# pcb_tcc_v2.net
KiCad netlist of a schematic drawn in EAGLE
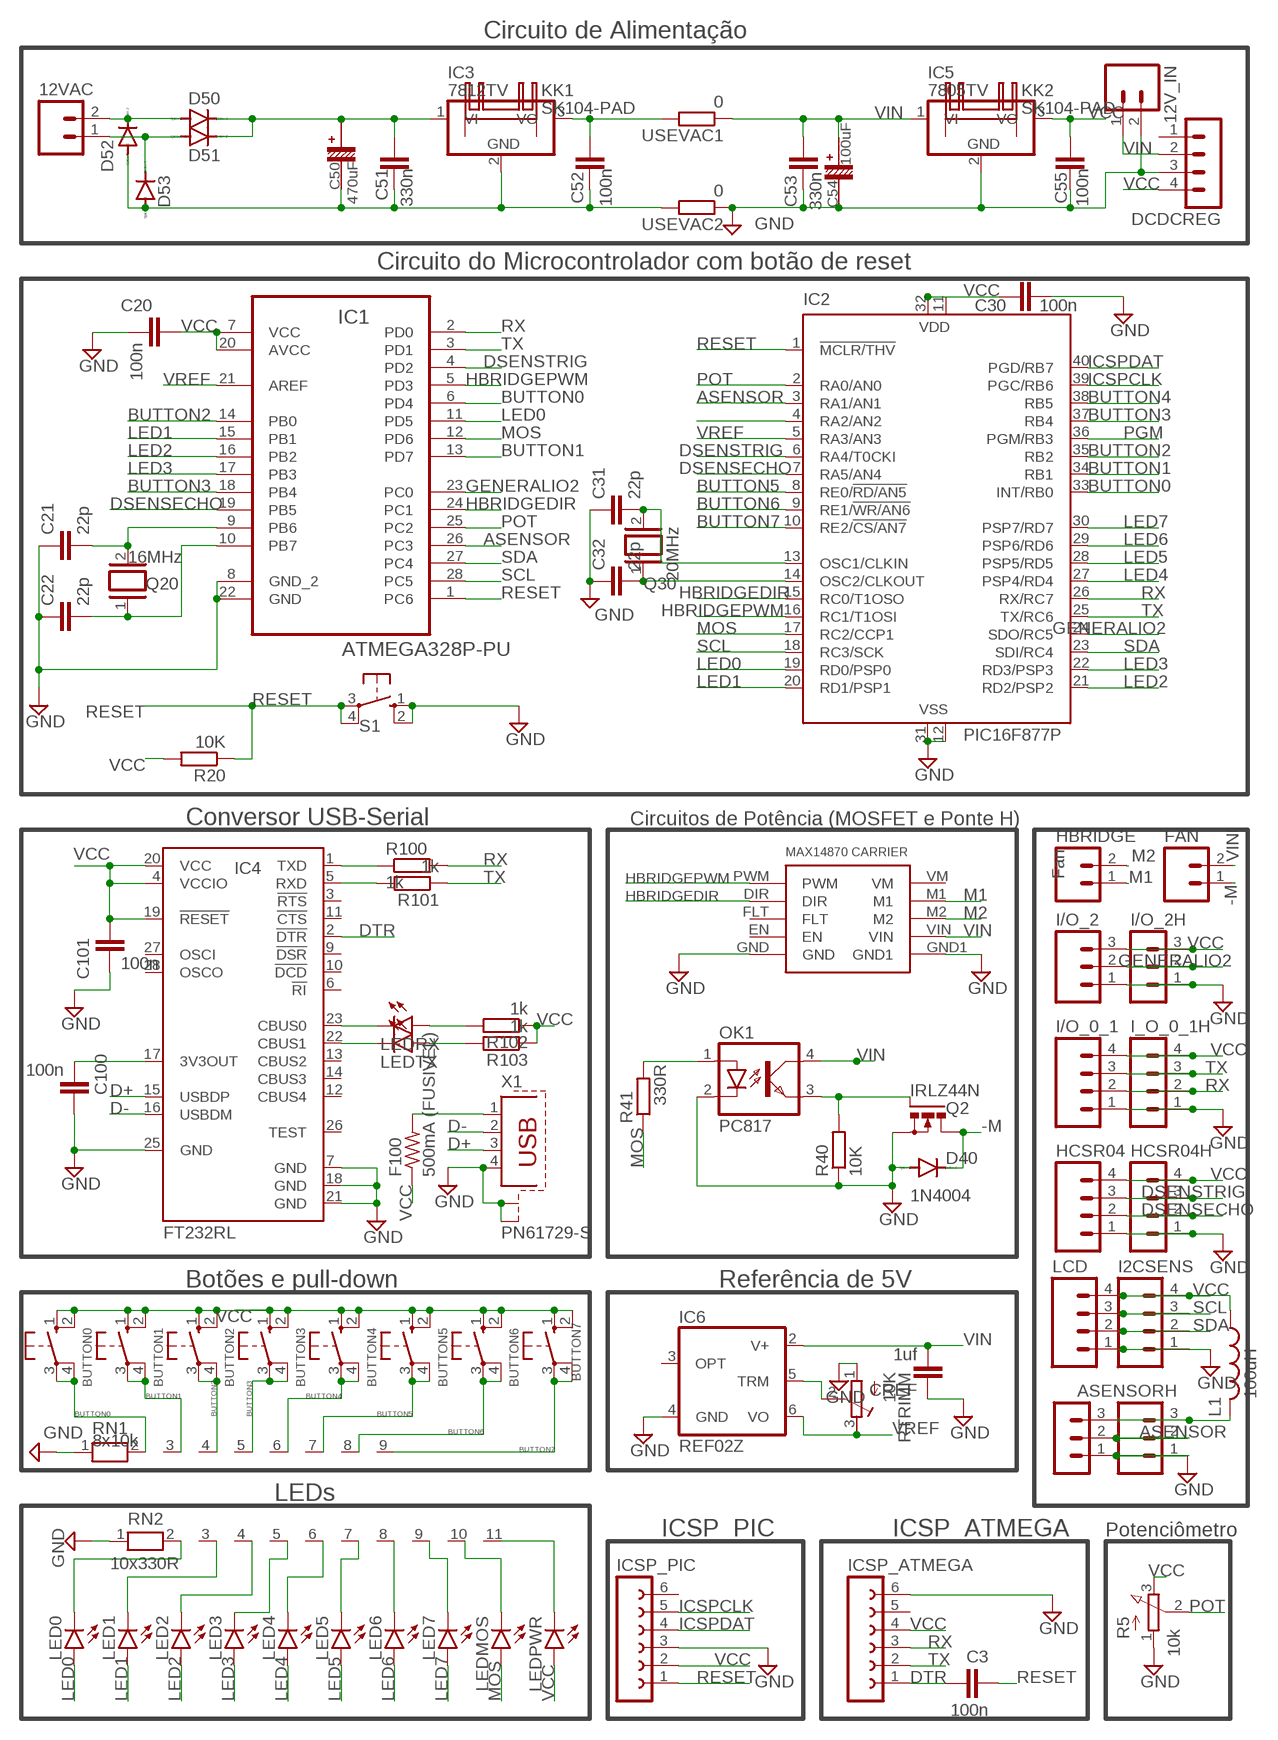
[diagram p0: schematic, sheet 1]

(export (version "E")
  (design (tool "Eeschema 10.0.6"))
  (components
    (comp (ref "12VAC")
      (value "M02")
      (footprint "eagle-import:02P")
      (libsource (lib "eagle-import") (part "M02"))
    )
    (comp (ref "12V_IN")
      (value "M02")
      (footprint "eagle-import:02P")
      (libsource (lib "eagle-import") (part "M02"))
    )
    (comp (ref "ASENSOR")
      (value "M03")
      (footprint "eagle-import:03P")
      (libsource (lib "eagle-import") (part "M03"))
    )
    (comp (ref "ASENSORH")
      (value "MA03-1")
      (footprint "eagle-import:MA03-1")
      (libsource (lib "eagle-import") (part "MA03-1"))
    )
    (comp (ref "BUTTON0")
      (value "10-XX")
      (footprint "eagle-import:B3F-10XX")
      (fields (field (name "MPN") "B3F-1000"))
      (libsource (lib "eagle-import") (part "10-XX"))
    )
    (comp (ref "BUTTON1")
      (value "10-XX")
      (footprint "eagle-import:B3F-10XX")
      (fields (field (name "MPN") "B3F-1000"))
      (libsource (lib "eagle-import") (part "10-XX"))
    )
    (comp (ref "BUTTON2")
      (value "10-XX")
      (footprint "eagle-import:B3F-10XX")
      (fields (field (name "MPN") "B3F-1000"))
      (libsource (lib "eagle-import") (part "10-XX"))
    )
    (comp (ref "BUTTON3")
      (value "10-XX")
      (footprint "eagle-import:B3F-10XX")
      (fields (field (name "MPN") "B3F-1000"))
      (libsource (lib "eagle-import") (part "10-XX"))
    )
    (comp (ref "BUTTON4")
      (value "10-XX")
      (footprint "eagle-import:B3F-10XX")
      (fields (field (name "MPN") "B3F-1000"))
      (libsource (lib "eagle-import") (part "10-XX"))
    )
    (comp (ref "BUTTON5")
      (value "10-XX")
      (footprint "eagle-import:B3F-10XX")
      (fields (field (name "MPN") "B3F-1000"))
      (libsource (lib "eagle-import") (part "10-XX"))
    )
    (comp (ref "BUTTON6")
      (value "10-XX")
      (footprint "eagle-import:B3F-10XX")
      (fields (field (name "MPN") "B3F-1000"))
      (libsource (lib "eagle-import") (part "10-XX"))
    )
    (comp (ref "BUTTON7")
      (value "10-XX")
      (footprint "eagle-import:B3F-10XX")
      (fields (field (name "MPN") "B3F-1000"))
      (libsource (lib "eagle-import") (part "10-XX"))
    )
    (comp (ref "C3")
      (value "100n")
      (footprint "eagle-import:C5B2.5")
      (libsource (lib "eagle-import") (part "C5/2.5"))
    )
    (comp (ref "C20")
      (value "100n")
      (footprint "eagle-import:C5B2.5")
      (libsource (lib "eagle-import") (part "C5/2.5"))
    )
    (comp (ref "C21")
      (value "22p")
      (footprint "eagle-import:C5B2.5")
      (libsource (lib "eagle-import") (part "C5/2.5"))
    )
    (comp (ref "C22")
      (value "22p")
      (footprint "eagle-import:C5B2.5")
      (libsource (lib "eagle-import") (part "C5/2.5"))
    )
    (comp (ref "C30")
      (value "100n")
      (footprint "eagle-import:C5B2.5")
      (libsource (lib "eagle-import") (part "C5/2.5"))
    )
    (comp (ref "C31")
      (value "22p")
      (footprint "eagle-import:C5B2.5")
      (libsource (lib "eagle-import") (part "C5/2.5"))
    )
    (comp (ref "C32")
      (value "22p")
      (footprint "eagle-import:C5B2.5")
      (libsource (lib "eagle-import") (part "C5/2.5"))
    )
    (comp (ref "C50")
      (value "470uF")
      (footprint "eagle-import:16V-10-5.08")
      (libsource (lib "eagle-import") (part "CE-16V-10-5.08"))
    )
    (comp (ref "C51")
      (value "330n")
      (footprint "eagle-import:C5B2.5")
      (libsource (lib "eagle-import") (part "C5/2.5"))
    )
    (comp (ref "C52")
      (value "100n")
      (footprint "eagle-import:C5B2.5")
      (libsource (lib "eagle-import") (part "C5/2.5"))
    )
    (comp (ref "C53")
      (value "330n")
      (footprint "eagle-import:C5B2.5")
      (libsource (lib "eagle-import") (part "C5/2.5"))
    )
    (comp (ref "C54")
      (value "100uF")
      (footprint "eagle-import:16V-6.3-2.54")
      (libsource (lib "eagle-import") (part "CE-16V-06.3-2.54"))
    )
    (comp (ref "C55")
      (value "100n")
      (footprint "eagle-import:C5B2.5")
      (libsource (lib "eagle-import") (part "C5/2.5"))
    )
    (comp (ref "C100")
      (value "100n")
      (footprint "eagle-import:C5B2.5")
      (libsource (lib "eagle-import") (part "C5/2.5"))
    )
    (comp (ref "C101")
      (value "100n")
      (footprint "eagle-import:C5B2.5")
      (libsource (lib "eagle-import") (part "C5/2.5"))
    )
    (comp (ref "CREF")
      (value "1uf")
      (footprint "eagle-import:C2.5-2")
      (libsource (lib "eagle-import") (part "C2.5/2"))
    )
    (comp (ref "D40")
      (value "1N4004")
      (footprint "eagle-import:DO41-10")
      (libsource (lib "eagle-import") (part "1N4004"))
    )
    (comp (ref "D50")
      (value "1N4004")
      (footprint "eagle-import:DO41-10")
      (libsource (lib "eagle-import") (part "1N4004"))
    )
    (comp (ref "D51")
      (value "1N4004")
      (footprint "eagle-import:DO41-10")
      (libsource (lib "eagle-import") (part "1N4004"))
    )
    (comp (ref "D52")
      (value "1N4004")
      (footprint "eagle-import:DO41-10")
      (libsource (lib "eagle-import") (part "1N4004"))
    )
    (comp (ref "D53")
      (value "1N4004")
      (footprint "eagle-import:DO41-10")
      (libsource (lib "eagle-import") (part "1N4004"))
    )
    (comp (ref "DCDCREG")
      (value "MA04-1")
      (footprint "eagle-import:MA04-1")
      (libsource (lib "eagle-import") (part "MA04-1"))
    )
    (comp (ref "F100")
      (value "500mA (FUSIVEL)")
      (footprint "eagle-import:R1206")
      (libsource (lib "eagle-import") (part "R-US_R1206"))
    )
    (comp (ref "FAN")
      (value "M02")
      (footprint "eagle-import:02P")
      (libsource (lib "eagle-import") (part "M02"))
    )
    (comp (ref "HBRIDGE")
      (value "M02")
      (footprint "eagle-import:02P")
      (libsource (lib "eagle-import") (part "M02"))
    )
    (comp (ref "HCSR04")
      (value "M04")
      (footprint "eagle-import:04P")
      (libsource (lib "eagle-import") (part "M04"))
    )
    (comp (ref "HCSR04H")
      (value "MA04-1")
      (footprint "eagle-import:MA04-1")
      (libsource (lib "eagle-import") (part "MA04-1"))
    )
    (comp (ref "I/O_0_1")
      (value "M04")
      (footprint "eagle-import:04P")
      (libsource (lib "eagle-import") (part "M04"))
    )
    (comp (ref "I/O_2")
      (value "M03")
      (footprint "eagle-import:03P")
      (libsource (lib "eagle-import") (part "M03"))
    )
    (comp (ref "I/O_2H")
      (value "MA03-1")
      (footprint "eagle-import:MA03-1")
      (libsource (lib "eagle-import") (part "MA03-1"))
    )
    (comp (ref "I2CSENS")
      (value "M04")
      (footprint "eagle-import:04P")
      (libsource (lib "eagle-import") (part "M04"))
    )
    (comp (ref "IC1")
      (value "ATMEGA328P-PU")
      (footprint "eagle-import:DIP254P762X457-28")
      (libsource (lib "eagle-import") (part "ATMEGA328P-PU"))
    )
    (comp (ref "IC2")
      (value "PIC16F877P")
      (footprint "eagle-import:DIL40")
      (fields (field (name "MF") "MICROCHIP") (field (name "MPN") "PIC16F877-04/P"))
      (libsource (lib "eagle-import") (part "PIC16F87P7"))
    )
    (comp (ref "IC3")
      (value "7812TV")
      (footprint "eagle-import:TO220V")
      (libsource (lib "eagle-import") (part "78TV12"))
    )
    (comp (ref "IC4")
      (value "FT232RL")
      (footprint "eagle-import:SSOP28")
      (libsource (lib "eagle-import") (part "FT232RL"))
    )
    (comp (ref "IC5")
      (value "7805TV")
      (footprint "eagle-import:TO220V")
      (libsource (lib "eagle-import") (part "78TV05"))
    )
    (comp (ref "IC6")
      (value "REF02Z")
      (footprint "eagle-import:DIL08")
      (libsource (lib "eagle-import") (part "REF02Z"))
    )
    (comp (ref "ICSP_ATMEGA")
      (value "FE06-1")
      (footprint "eagle-import:FE06")
      (libsource (lib "eagle-import") (part "FE06-1"))
    )
    (comp (ref "ICSP_PIC")
      (value "FE06-1")
      (footprint "eagle-import:FE06")
      (libsource (lib "eagle-import") (part "FE06-1"))
    )
    (comp (ref "I_O_0_1H")
      (value "MA04-1")
      (footprint "eagle-import:MA04-1")
      (libsource (lib "eagle-import") (part "MA04-1"))
    )
    (comp (ref "KK1")
      (value "SK104-PAD")
      (footprint "eagle-import:SK104-PAD")
      (libsource (lib "eagle-import") (part "SK104-PAD"))
    )
    (comp (ref "KK2")
      (value "SK104-PAD")
      (footprint "eagle-import:SK104-PAD")
      (libsource (lib "eagle-import") (part "SK104-PAD"))
    )
    (comp (ref "L1")
      (value "100uH")
      (footprint "eagle-import:0204_7")
      (libsource (lib "eagle-import") (part "L-US0204/7"))
    )
    (comp (ref "LCD")
      (value "M04")
      (footprint "eagle-import:04P")
      (libsource (lib "eagle-import") (part "M04"))
    )
    (comp (ref "LED0")
      (value "LED3MM")
      (footprint "eagle-import:LED3MM")
      (libsource (lib "eagle-import") (part "LED3MM"))
    )
    (comp (ref "LED1")
      (value "LED3MM")
      (footprint "eagle-import:LED3MM")
      (libsource (lib "eagle-import") (part "LED3MM"))
    )
    (comp (ref "LED2")
      (value "LED3MM")
      (footprint "eagle-import:LED3MM")
      (libsource (lib "eagle-import") (part "LED3MM"))
    )
    (comp (ref "LED3")
      (value "LED3MM")
      (footprint "eagle-import:LED3MM")
      (libsource (lib "eagle-import") (part "LED3MM"))
    )
    (comp (ref "LED4")
      (value "LED3MM")
      (footprint "eagle-import:LED3MM")
      (libsource (lib "eagle-import") (part "LED3MM"))
    )
    (comp (ref "LED5")
      (value "LED3MM")
      (footprint "eagle-import:LED3MM")
      (libsource (lib "eagle-import") (part "LED3MM"))
    )
    (comp (ref "LED6")
      (value "LED3MM")
      (footprint "eagle-import:LED3MM")
      (libsource (lib "eagle-import") (part "LED3MM"))
    )
    (comp (ref "LED7")
      (value "LED3MM")
      (footprint "eagle-import:LED3MM")
      (libsource (lib "eagle-import") (part "LED3MM"))
    )
    (comp (ref "LEDMOS")
      (value "LED3MM")
      (footprint "eagle-import:LED3MM")
      (libsource (lib "eagle-import") (part "LED3MM"))
    )
    (comp (ref "LEDPWR")
      (value "LED3MM")
      (footprint "eagle-import:LED3MM")
      (libsource (lib "eagle-import") (part "LED3MM"))
    )
    (comp (ref "LEDRX")
      (value "LED3MM")
      (footprint "eagle-import:LED3MM")
      (libsource (lib "eagle-import") (part "LED3MM"))
    )
    (comp (ref "LEDTX")
      (value "LED3MM")
      (footprint "eagle-import:LED3MM")
      (libsource (lib "eagle-import") (part "LED3MM"))
    )
    (comp (ref "OK1")
      (value "PC817")
      (footprint "eagle-import:DIL04")
      (fields (field (name "MPN") "PC817X4J000F"))
      (libsource (lib "eagle-import") (part "PC817"))
    )
    (comp (ref "Q2")
      (value "IRLZ44N")
      (footprint "eagle-import:TO220BV")
      (libsource (lib "eagle-import") (part "IRF512"))
    )
    (comp (ref "Q20")
      (value "16MHz")
      (footprint "eagle-import:QS")
      (libsource (lib "eagle-import") (part "XTAL/S"))
    )
    (comp (ref "Q30")
      (value "20MHz")
      (footprint "eagle-import:QS")
      (libsource (lib "eagle-import") (part "XTAL/S"))
    )
    (comp (ref "R5")
      (value "10k")
      (footprint "eagle-import:3RP_1610N")
      (libsource (lib "eagle-import") (part "3RP/1610N"))
    )
    (comp (ref "R20")
      (value "10K")
      (footprint "eagle-import:0207_10")
      (libsource (lib "eagle-import") (part "R-EU_0207/10"))
    )
    (comp (ref "R40")
      (value "10K")
      (footprint "eagle-import:0207_10")
      (libsource (lib "eagle-import") (part "R-EU_0207/10"))
    )
    (comp (ref "R41")
      (value "330R")
      (footprint "eagle-import:0207_7")
      (libsource (lib "eagle-import") (part "R-EU_0207/7"))
    )
    (comp (ref "R100")
      (value "1k")
      (footprint "eagle-import:0207_10")
      (libsource (lib "eagle-import") (part "R-EU_0207/10"))
    )
    (comp (ref "R101")
      (value "1k")
      (footprint "eagle-import:0207_10")
      (libsource (lib "eagle-import") (part "R-EU_0207/10"))
    )
    (comp (ref "R102")
      (value "1k")
      (footprint "eagle-import:0207_10")
      (libsource (lib "eagle-import") (part "R-EU_0207/10"))
    )
    (comp (ref "R103")
      (value "1k")
      (footprint "eagle-import:0207_10")
      (libsource (lib "eagle-import") (part "R-EU_0207/10"))
    )
    (comp (ref "RN1")
      (value "8x10k")
      (footprint "eagle-import:RN-9")
      (libsource (lib "eagle-import") (part "RN08"))
    )
    (comp (ref "RN2")
      (value "10x330R")
      (footprint "eagle-import:RN-11")
      (libsource (lib "eagle-import") (part "RN10"))
    )
    (comp (ref "RTRIMM")
      (value "10K")
      (footprint "eagle-import:RTRIM3296W")
      (libsource (lib "eagle-import") (part "R-TRIMM3296W"))
    )
    (comp (ref "S1")
      (value "10-XX")
      (footprint "eagle-import:B3F-10XX")
      (fields (field (name "MPN") "B3F-1000"))
      (libsource (lib "eagle-import") (part "10-XX"))
    )
    (comp (ref "U$1")
      (value "MAX14870")
      (footprint "eagle-import:POLOLU_CARRIER")
      (libsource (lib "eagle-import") (part "MAX14870"))
    )
    (comp (ref "USEVAC1")
      (value "0")
      (footprint "eagle-import:0207_10")
      (libsource (lib "eagle-import") (part "R-EU_0207/10"))
    )
    (comp (ref "USEVAC2")
      (value "0")
      (footprint "eagle-import:0207_10")
      (libsource (lib "eagle-import") (part "R-EU_0207/10"))
    )
    (comp (ref "X1")
      (value "PN61729-S")
      (footprint "eagle-import:PN61729-S")
      (libsource (lib "eagle-import") (part "PN61729-S"))
    )
  )
  (nets
    (net (code "1") (name "/-M") (class "Default")
      (node (ref "D40") (pin "C") (pinfunction "C_C") (pintype "passive"))
      (node (ref "FAN") (pin "1") (pinfunction "1_1") (pintype "passive"))
      (node (ref "Q2") (pin "D") (pinfunction "D_D") (pintype "passive"))
    )
    (net (code "2") (name "/ASENSOR") (class "Default")
      (node (ref "ASENSOR") (pin "2") (pinfunction "2_2") (pintype "passive"))
      (node (ref "ASENSORH") (pin "2") (pinfunction "2_2") (pintype "passive"))
      (node (ref "IC1") (pin "26") (pinfunction "PC3_26") (pintype "bidirectional"))
      (node (ref "IC2") (pin "3") (pinfunction "RA1/AN1_3") (pintype "bidirectional"))
    )
    (net (code "3") (name "/BUTTON0") (class "Default")
      (node (ref "BUTTON0") (pin "3") (pinfunction "P_3") (pintype "passive"))
      (node (ref "BUTTON0") (pin "4") (pinfunction "P1_4") (pintype "passive"))
      (node (ref "IC1") (pin "6") (pinfunction "PD4_6") (pintype "bidirectional"))
      (node (ref "IC2") (pin "33") (pinfunction "INT/RB0_33") (pintype "bidirectional"))
      (node (ref "RN1") (pin "2") (pinfunction "2_2") (pintype "passive"))
    )
    (net (code "4") (name "/BUTTON1") (class "Default")
      (node (ref "BUTTON1") (pin "3") (pinfunction "P_3") (pintype "passive"))
      (node (ref "BUTTON1") (pin "4") (pinfunction "P1_4") (pintype "passive"))
      (node (ref "IC1") (pin "13") (pinfunction "PD7_13") (pintype "bidirectional"))
      (node (ref "IC2") (pin "34") (pinfunction "RB1_34") (pintype "bidirectional"))
      (node (ref "RN1") (pin "3") (pinfunction "3_3") (pintype "passive"))
    )
    (net (code "5") (name "/BUTTON2") (class "Default")
      (node (ref "BUTTON2") (pin "3") (pinfunction "P_3") (pintype "passive"))
      (node (ref "BUTTON2") (pin "4") (pinfunction "P1_4") (pintype "passive"))
      (node (ref "IC1") (pin "14") (pinfunction "PB0_14") (pintype "bidirectional"))
      (node (ref "IC2") (pin "35") (pinfunction "RB2_35") (pintype "bidirectional"))
      (node (ref "RN1") (pin "4") (pinfunction "4_4") (pintype "passive"))
    )
    (net (code "6") (name "/BUTTON3") (class "Default")
      (node (ref "BUTTON3") (pin "3") (pinfunction "P_3") (pintype "passive"))
      (node (ref "BUTTON3") (pin "4") (pinfunction "P1_4") (pintype "passive"))
      (node (ref "IC1") (pin "18") (pinfunction "PB4_18") (pintype "bidirectional"))
      (node (ref "IC2") (pin "37") (pinfunction "RB4_37") (pintype "bidirectional"))
      (node (ref "RN1") (pin "5") (pinfunction "5_5") (pintype "passive"))
    )
    (net (code "7") (name "/BUTTON4") (class "Default")
      (node (ref "BUTTON4") (pin "3") (pinfunction "P_3") (pintype "passive"))
      (node (ref "BUTTON4") (pin "4") (pinfunction "P1_4") (pintype "passive"))
      (node (ref "IC2") (pin "38") (pinfunction "RB5_38") (pintype "bidirectional"))
      (node (ref "RN1") (pin "6") (pinfunction "6_6") (pintype "passive"))
    )
    (net (code "8") (name "/BUTTON5") (class "Default")
      (node (ref "BUTTON5") (pin "3") (pinfunction "P_3") (pintype "passive"))
      (node (ref "BUTTON5") (pin "4") (pinfunction "P1_4") (pintype "passive"))
      (node (ref "IC2") (pin "8") (pinfunction "RE0/~{RD/AN5}_8") (pintype "bidirectional"))
      (node (ref "RN1") (pin "7") (pinfunction "7_7") (pintype "passive"))
    )
    (net (code "9") (name "/BUTTON6") (class "Default")
      (node (ref "BUTTON6") (pin "3") (pinfunction "P_3") (pintype "passive"))
      (node (ref "BUTTON6") (pin "4") (pinfunction "P1_4") (pintype "passive"))
      (node (ref "IC2") (pin "9") (pinfunction "RE1/~{WR/AN6}_9") (pintype "bidirectional"))
      (node (ref "RN1") (pin "8") (pinfunction "8_8") (pintype "passive"))
    )
    (net (code "10") (name "/BUTTON7") (class "Default")
      (node (ref "BUTTON7") (pin "3") (pinfunction "P_3") (pintype "passive"))
      (node (ref "BUTTON7") (pin "4") (pinfunction "P1_4") (pintype "passive"))
      (node (ref "IC2") (pin "10") (pinfunction "RE2/~{CS/AN7}_10") (pintype "bidirectional"))
      (node (ref "RN1") (pin "9") (pinfunction "9_9") (pintype "passive"))
    )
    (net (code "11") (name "/D+") (class "Default")
      (node (ref "IC4") (pin "15") (pinfunction "USBDP_15") (pintype "bidirectional"))
      (node (ref "X1") (pin "3") (pinfunction "3_3") (pintype "passive"))
    )
    (net (code "12") (name "/D-") (class "Default")
      (node (ref "IC4") (pin "16") (pinfunction "USBDM_16") (pintype "bidirectional"))
      (node (ref "X1") (pin "2") (pinfunction "2_2") (pintype "passive"))
    )
    (net (code "13") (name "/DSENSECHO") (class "Default")
      (node (ref "HCSR04") (pin "2") (pinfunction "2_2") (pintype "passive"))
      (node (ref "HCSR04H") (pin "2") (pinfunction "2_2") (pintype "passive"))
      (node (ref "IC1") (pin "19") (pinfunction "PB5_19") (pintype "bidirectional"))
      (node (ref "IC2") (pin "7") (pinfunction "RA5/AN4_7") (pintype "bidirectional"))
    )
    (net (code "14") (name "/DSENSTRIG") (class "Default")
      (node (ref "HCSR04") (pin "3") (pinfunction "3_3") (pintype "passive"))
      (node (ref "HCSR04H") (pin "3") (pinfunction "3_3") (pintype "passive"))
      (node (ref "IC1") (pin "4") (pinfunction "PD2_4") (pintype "bidirectional"))
      (node (ref "IC2") (pin "6") (pinfunction "RA4/T0CKI_6") (pintype "bidirectional"))
    )
    (net (code "15") (name "/DTR") (class "Default")
      (node (ref "C3") (pin "1") (pinfunction "1_1") (pintype "passive"))
      (node (ref "IC4") (pin "2") (pinfunction "~{DTR}_2") (pintype "output"))
      (node (ref "ICSP_ATMEGA") (pin "1") (pinfunction "1_1") (pintype "passive"))
    )
    (net (code "16") (name "/GENERALIO2") (class "Default")
      (node (ref "I/O_2") (pin "2") (pinfunction "2_2") (pintype "passive"))
      (node (ref "I/O_2H") (pin "2") (pinfunction "2_2") (pintype "passive"))
      (node (ref "IC1") (pin "23") (pinfunction "PC0_23") (pintype "bidirectional"))
      (node (ref "IC2") (pin "24") (pinfunction "SDO/RC5_24") (pintype "bidirectional"))
    )
    (net (code "17") (name "/HBRIDGEDIR") (class "Default")
      (node (ref "IC1") (pin "24") (pinfunction "PC1_24") (pintype "bidirectional"))
      (node (ref "IC2") (pin "15") (pinfunction "RC0/T1OSO_15") (pintype "bidirectional"))
      (node (ref "U$1") (pin "DIR") (pinfunction "DIR_DIR") (pintype "bidirectional"))
    )
    (net (code "18") (name "/HBRIDGEPWM") (class "Default")
      (node (ref "IC1") (pin "5") (pinfunction "PD3_5") (pintype "bidirectional"))
      (node (ref "IC2") (pin "16") (pinfunction "RC1/T1OSI_16") (pintype "bidirectional"))
      (node (ref "U$1") (pin "PWM") (pinfunction "PWM_PWM") (pintype "bidirectional"))
    )
    (net (code "19") (name "/ICSPCLK") (class "Default")
      (node (ref "IC2") (pin "39") (pinfunction "PGC/RB6_39") (pintype "bidirectional"))
      (node (ref "ICSP_PIC") (pin "5") (pinfunction "5_5") (pintype "passive"))
    )
    (net (code "20") (name "/ICSPDAT") (class "Default")
      (node (ref "IC2") (pin "40") (pinfunction "PGD/RB7_40") (pintype "bidirectional"))
      (node (ref "ICSP_PIC") (pin "4") (pinfunction "4_4") (pintype "passive"))
    )
    (net (code "21") (name "/LED0") (class "Default")
      (node (ref "IC1") (pin "11") (pinfunction "PD5_11") (pintype "bidirectional"))
      (node (ref "IC2") (pin "19") (pinfunction "RD0/PSP0_19") (pintype "bidirectional"))
      (node (ref "LED0") (pin "A") (pinfunction "A_A") (pintype "passive"))
    )
    (net (code "22") (name "/LED1") (class "Default")
      (node (ref "IC1") (pin "15") (pinfunction "PB1_15") (pintype "bidirectional"))
      (node (ref "IC2") (pin "20") (pinfunction "RD1/PSP1_20") (pintype "bidirectional"))
      (node (ref "LED1") (pin "A") (pinfunction "A_A") (pintype "passive"))
    )
    (net (code "23") (name "/LED2") (class "Default")
      (node (ref "IC1") (pin "16") (pinfunction "PB2_16") (pintype "bidirectional"))
      (node (ref "IC2") (pin "21") (pinfunction "RD2/PSP2_21") (pintype "bidirectional"))
      (node (ref "LED2") (pin "A") (pinfunction "A_A") (pintype "passive"))
    )
    (net (code "24") (name "/LED3") (class "Default")
      (node (ref "IC1") (pin "17") (pinfunction "PB3_17") (pintype "bidirectional"))
      (node (ref "IC2") (pin "22") (pinfunction "RD3/PSP3_22") (pintype "bidirectional"))
      (node (ref "LED3") (pin "A") (pinfunction "A_A") (pintype "passive"))
    )
    (net (code "25") (name "/LED4") (class "Default")
      (node (ref "IC2") (pin "27") (pinfunction "PSP4/RD4_27") (pintype "bidirectional"))
      (node (ref "LED4") (pin "A") (pinfunction "A_A") (pintype "passive"))
    )
    (net (code "26") (name "/LED5") (class "Default")
      (node (ref "IC2") (pin "28") (pinfunction "PSP5/RD5_28") (pintype "bidirectional"))
      (node (ref "LED5") (pin "A") (pinfunction "A_A") (pintype "passive"))
    )
    (net (code "27") (name "/LED6") (class "Default")
      (node (ref "IC2") (pin "29") (pinfunction "PSP6/RD6_29") (pintype "bidirectional"))
      (node (ref "LED6") (pin "A") (pinfunction "A_A") (pintype "passive"))
    )
    (net (code "28") (name "/LED7") (class "Default")
      (node (ref "IC2") (pin "30") (pinfunction "PSP7/RD7_30") (pintype "bidirectional"))
      (node (ref "LED7") (pin "A") (pinfunction "A_A") (pintype "passive"))
    )
    (net (code "29") (name "/M1") (class "Default")
      (node (ref "HBRIDGE") (pin "1") (pinfunction "1_1") (pintype "passive"))
      (node (ref "U$1") (pin "M1") (pinfunction "M1_M1") (pintype "bidirectional"))
    )
    (net (code "30") (name "/M2") (class "Default")
      (node (ref "HBRIDGE") (pin "2") (pinfunction "2_2") (pintype "passive"))
      (node (ref "U$1") (pin "M2") (pinfunction "M2_M2") (pintype "bidirectional"))
    )
    (net (code "31") (name "/MOS") (class "Default")
      (node (ref "IC1") (pin "12") (pinfunction "PD6_12") (pintype "bidirectional"))
      (node (ref "IC2") (pin "17") (pinfunction "RC2/CCP1_17") (pintype "bidirectional"))
      (node (ref "LEDMOS") (pin "A") (pinfunction "A_A") (pintype "passive"))
      (node (ref "R41") (pin "1") (pinfunction "1_1") (pintype "passive"))
    )
    (net (code "32") (name "/PGM") (class "Default")
      (node (ref "IC2") (pin "36") (pinfunction "PGM/RB3_36") (pintype "bidirectional"))
    )
    (net (code "33") (name "/POT") (class "Default")
      (node (ref "IC1") (pin "25") (pinfunction "PC2_25") (pintype "bidirectional"))
      (node (ref "IC2") (pin "2") (pinfunction "RA0/AN0_2") (pintype "bidirectional"))
      (node (ref "R5") (pin "2") (pinfunction "S_2") (pintype "passive"))
    )
    (net (code "34") (name "/RESET") (class "Default")
      (node (ref "C3") (pin "2") (pinfunction "2_2") (pintype "passive"))
      (node (ref "IC1") (pin "1") (pinfunction "PC6_1") (pintype "bidirectional"))
      (node (ref "IC2") (pin "1") (pinfunction "~{MCLR/THV}_1") (pintype "input"))
      (node (ref "ICSP_PIC") (pin "1") (pinfunction "1_1") (pintype "passive"))
      (node (ref "R20") (pin "1") (pinfunction "1_1") (pintype "passive"))
      (node (ref "S1") (pin "3") (pinfunction "P_3") (pintype "passive"))
      (node (ref "S1") (pin "4") (pinfunction "P1_4") (pintype "passive"))
    )
    (net (code "35") (name "/RX") (class "Default")
      (node (ref "I/O_0_1") (pin "2") (pinfunction "2_2") (pintype "passive"))
      (node (ref "IC1") (pin "2") (pinfunction "PD0_2") (pintype "bidirectional"))
      (node (ref "IC2") (pin "26") (pinfunction "RX/RC7_26") (pintype "bidirectional"))
      (node (ref "ICSP_ATMEGA") (pin "3") (pinfunction "3_3") (pintype "passive"))
      (node (ref "I_O_0_1H") (pin "2") (pinfunction "2_2") (pintype "passive"))
      (node (ref "R100") (pin "2") (pinfunction "2_2") (pintype "passive"))
    )
    (net (code "36") (name "/SCL") (class "Default")
      (node (ref "I2CSENS") (pin "3") (pinfunction "3_3") (pintype "passive"))
      (node (ref "IC1") (pin "28") (pinfunction "PC5_28") (pintype "bidirectional"))
      (node (ref "IC2") (pin "18") (pinfunction "RC3/SCK_18") (pintype "bidirectional"))
      (node (ref "LCD") (pin "3") (pinfunction "3_3") (pintype "passive"))
    )
    (net (code "37") (name "/SDA") (class "Default")
      (node (ref "I2CSENS") (pin "2") (pinfunction "2_2") (pintype "passive"))
      (node (ref "IC1") (pin "27") (pinfunction "PC4_27") (pintype "bidirectional"))
      (node (ref "IC2") (pin "23") (pinfunction "SDI/RC4_23") (pintype "bidirectional"))
      (node (ref "LCD") (pin "2") (pinfunction "2_2") (pintype "passive"))
    )
    (net (code "38") (name "/TX") (class "Default")
      (node (ref "I/O_0_1") (pin "3") (pinfunction "3_3") (pintype "passive"))
      (node (ref "IC1") (pin "3") (pinfunction "PD1_3") (pintype "bidirectional"))
      (node (ref "IC2") (pin "25") (pinfunction "TX/RC6_25") (pintype "bidirectional"))
      (node (ref "ICSP_ATMEGA") (pin "2") (pinfunction "2_2") (pintype "passive"))
      (node (ref "I_O_0_1H") (pin "3") (pinfunction "3_3") (pintype "passive"))
      (node (ref "R101") (pin "1") (pinfunction "1_1") (pintype "passive"))
    )
    (net (code "39") (name "/VCC") (class "Default")
      (node (ref "BUTTON0") (pin "1") (pinfunction "S_1") (pintype "passive"))
      (node (ref "BUTTON0") (pin "2") (pinfunction "S1_2") (pintype "passive"))
      (node (ref "BUTTON1") (pin "1") (pinfunction "S_1") (pintype "passive"))
      (node (ref "BUTTON1") (pin "2") (pinfunction "S1_2") (pintype "passive"))
      (node (ref "BUTTON2") (pin "1") (pinfunction "S_1") (pintype "passive"))
      (node (ref "BUTTON2") (pin "2") (pinfunction "S1_2") (pintype "passive"))
      (node (ref "BUTTON3") (pin "1") (pinfunction "S_1") (pintype "passive"))
      (node (ref "BUTTON3") (pin "2") (pinfunction "S1_2") (pintype "passive"))
      (node (ref "BUTTON4") (pin "1") (pinfunction "S_1") (pintype "passive"))
      (node (ref "BUTTON4") (pin "2") (pinfunction "S1_2") (pintype "passive"))
      (node (ref "BUTTON5") (pin "1") (pinfunction "S_1") (pintype "passive"))
      (node (ref "BUTTON5") (pin "2") (pinfunction "S1_2") (pintype "passive"))
      (node (ref "BUTTON6") (pin "1") (pinfunction "S_1") (pintype "passive"))
      (node (ref "BUTTON6") (pin "2") (pinfunction "S1_2") (pintype "passive"))
      (node (ref "BUTTON7") (pin "1") (pinfunction "S_1") (pintype "passive"))
      (node (ref "BUTTON7") (pin "2") (pinfunction "S1_2") (pintype "passive"))
      (node (ref "C101") (pin "1") (pinfunction "1_1") (pintype "passive"))
      (node (ref "C20") (pin "1") (pinfunction "1_1") (pintype "passive"))
      (node (ref "C30") (pin "1") (pinfunction "1_1") (pintype "passive"))
      (node (ref "C55") (pin "2") (pinfunction "2_2") (pintype "passive"))
      (node (ref "DCDCREG") (pin "4") (pinfunction "4_4") (pintype "passive"))
      (node (ref "F100") (pin "1") (pinfunction "1_1") (pintype "passive"))
      (node (ref "HCSR04") (pin "4") (pinfunction "4_4") (pintype "passive"))
      (node (ref "HCSR04H") (pin "4") (pinfunction "4_4") (pintype "passive"))
      (node (ref "I/O_0_1") (pin "4") (pinfunction "4_4") (pintype "passive"))
      (node (ref "I/O_2") (pin "3") (pinfunction "3_3") (pintype "passive"))
      (node (ref "I/O_2H") (pin "3") (pinfunction "3_3") (pintype "passive"))
      (node (ref "I2CSENS") (pin "4") (pinfunction "4_4") (pintype "passive"))
      (node (ref "IC1") (pin "20") (pinfunction "AVCC_20") (pintype "power_in"))
      (node (ref "IC1") (pin "7") (pinfunction "VCC_7") (pintype "power_in"))
      (node (ref "IC2") (pin "11") (pinfunction "VDD_11") (pintype "power_in"))
      (node (ref "IC2") (pin "32") (pinfunction "VDD_32") (pintype "power_in"))
      (node (ref "IC4") (pin "19") (pinfunction "~{RESET}_19") (pintype "input"))
      (node (ref "IC4") (pin "20") (pinfunction "VCC_20") (pintype "power_in"))
      (node (ref "IC4") (pin "4") (pinfunction "VCCIO_4") (pintype "power_in"))
      (node (ref "IC5") (pin "3") (pinfunction "VO_3") (pintype "passive"))
      (node (ref "ICSP_ATMEGA") (pin "4") (pinfunction "4_4") (pintype "passive"))
      (node (ref "ICSP_PIC") (pin "2") (pinfunction "2_2") (pintype "passive"))
      (node (ref "I_O_0_1H") (pin "4") (pinfunction "4_4") (pintype "passive"))
      (node (ref "L1") (pin "1") (pinfunction "1_1") (pintype "passive"))
      (node (ref "LCD") (pin "4") (pinfunction "4_4") (pintype "passive"))
      (node (ref "LEDPWR") (pin "A") (pinfunction "A_A") (pintype "passive"))
      (node (ref "R102") (pin "1") (pinfunction "1_1") (pintype "passive"))
      (node (ref "R103") (pin "1") (pinfunction "1_1") (pintype "passive"))
      (node (ref "R20") (pin "2") (pinfunction "2_2") (pintype "passive"))
      (node (ref "R5") (pin "3") (pinfunction "E_3") (pintype "passive"))
    )
    (net (code "40") (name "/VIN") (class "Default")
      (node (ref "12V_IN") (pin "1") (pinfunction "1_1") (pintype "passive"))
      (node (ref "C53") (pin "2") (pinfunction "2_2") (pintype "passive"))
      (node (ref "C54") (pin "+") (pinfunction "+_+") (pintype "passive"))
      (node (ref "CREF") (pin "2") (pinfunction "2_2") (pintype "passive"))
      (node (ref "DCDCREG") (pin "2") (pinfunction "2_2") (pintype "passive"))
      (node (ref "FAN") (pin "2") (pinfunction "2_2") (pintype "passive"))
      (node (ref "IC5") (pin "1") (pinfunction "VI_1") (pintype "input"))
      (node (ref "IC6") (pin "2") (pinfunction "V+_2") (pintype "power_in"))
      (node (ref "OK1") (pin "4") (pinfunction "COL_4") (pintype "passive"))
      (node (ref "U$1") (pin "VIN") (pinfunction "VIN_VIN") (pintype "bidirectional"))
      (node (ref "USEVAC1") (pin "1") (pinfunction "1_1") (pintype "passive"))
    )
    (net (code "41") (name "/VREF") (class "Default")
      (node (ref "IC1") (pin "21") (pinfunction "AREF_21") (pintype "input"))
      (node (ref "IC2") (pin "5") (pinfunction "RA3/AN3_5") (pintype "bidirectional"))
      (node (ref "IC6") (pin "6") (pinfunction "VO_6") (pintype "output"))
      (node (ref "RTRIMM") (pin "3") (pinfunction "E_3") (pintype "passive"))
    )
    (net (code "42") (name "GND") (class "Default")
      (node (ref "12V_IN") (pin "2") (pinfunction "2_2") (pintype "passive"))
      (node (ref "ASENSOR") (pin "1") (pinfunction "1_1") (pintype "passive"))
      (node (ref "ASENSORH") (pin "1") (pinfunction "1_1") (pintype "passive"))
      (node (ref "C100") (pin "1") (pinfunction "1_1") (pintype "passive"))
      (node (ref "C101") (pin "2") (pinfunction "2_2") (pintype "passive"))
      (node (ref "C20") (pin "2") (pinfunction "2_2") (pintype "passive"))
      (node (ref "C21") (pin "1") (pinfunction "1_1") (pintype "passive"))
      (node (ref "C22") (pin "1") (pinfunction "1_1") (pintype "passive"))
      (node (ref "C30") (pin "2") (pinfunction "2_2") (pintype "passive"))
      (node (ref "C31") (pin "1") (pinfunction "1_1") (pintype "passive"))
      (node (ref "C32") (pin "1") (pinfunction "1_1") (pintype "passive"))
      (node (ref "C53") (pin "1") (pinfunction "1_1") (pintype "passive"))
      (node (ref "C54") (pin "-") (pinfunction "-_-") (pintype "passive"))
      (node (ref "C55") (pin "1") (pinfunction "1_1") (pintype "passive"))
      (node (ref "CREF") (pin "1") (pinfunction "1_1") (pintype "passive"))
      (node (ref "D40") (pin "A") (pinfunction "A_A") (pintype "passive"))
      (node (ref "DCDCREG") (pin "3") (pinfunction "3_3") (pintype "passive"))
      (node (ref "HCSR04") (pin "1") (pinfunction "1_1") (pintype "passive"))
      (node (ref "HCSR04H") (pin "1") (pinfunction "1_1") (pintype "passive"))
      (node (ref "I/O_0_1") (pin "1") (pinfunction "1_1") (pintype "passive"))
      (node (ref "I/O_2") (pin "1") (pinfunction "1_1") (pintype "passive"))
      (node (ref "I/O_2H") (pin "1") (pinfunction "1_1") (pintype "passive"))
      (node (ref "I2CSENS") (pin "1") (pinfunction "1_1") (pintype "passive"))
      (node (ref "IC1") (pin "22") (pinfunction "GND_22") (pintype "passive"))
      (node (ref "IC1") (pin "8") (pinfunction "GND_2_8") (pintype "passive"))
      (node (ref "IC2") (pin "12") (pinfunction "VSS_12") (pintype "power_in"))
      (node (ref "IC2") (pin "31") (pinfunction "VSS_31") (pintype "power_in"))
      (node (ref "IC4") (pin "18") (pinfunction "GND_18") (pintype "power_in"))
      (node (ref "IC4") (pin "21") (pinfunction "GND_21") (pintype "power_in"))
      (node (ref "IC4") (pin "25") (pinfunction "GND_25") (pintype "power_in"))
      (node (ref "IC4") (pin "7") (pinfunction "GND_7") (pintype "power_in"))
      (node (ref "IC5") (pin "2") (pinfunction "GND_2") (pintype "passive"))
      (node (ref "IC6") (pin "4") (pinfunction "GND_4") (pintype "power_in"))
      (node (ref "ICSP_ATMEGA") (pin "6") (pinfunction "6_6") (pintype "passive"))
      (node (ref "ICSP_PIC") (pin "3") (pinfunction "3_3") (pintype "passive"))
      (node (ref "I_O_0_1H") (pin "1") (pinfunction "1_1") (pintype "passive"))
      (node (ref "LCD") (pin "1") (pinfunction "1_1") (pintype "passive"))
      (node (ref "OK1") (pin "2") (pinfunction "C_2") (pintype "passive"))
      (node (ref "Q2") (pin "S") (pinfunction "S_S") (pintype "passive"))
      (node (ref "R40") (pin "1") (pinfunction "1_1") (pintype "passive"))
      (node (ref "R5") (pin "1") (pinfunction "A_1") (pintype "passive"))
      (node (ref "RN1") (pin "1") (pinfunction "1_1") (pintype "passive"))
      (node (ref "RN2") (pin "1") (pinfunction "1_1") (pintype "passive"))
      (node (ref "RTRIMM") (pin "1") (pinfunction "A_1") (pintype "passive"))
      (node (ref "S1") (pin "1") (pinfunction "S_1") (pintype "passive"))
      (node (ref "S1") (pin "2") (pinfunction "S1_2") (pintype "passive"))
      (node (ref "U$1") (pin "GND") (pinfunction "GND_GND") (pintype "bidirectional"))
      (node (ref "U$1") (pin "GND1") (pinfunction "GND1_GND1") (pintype "bidirectional"))
      (node (ref "USEVAC2") (pin "1") (pinfunction "1_1") (pintype "passive"))
      (node (ref "X1") (pin "4") (pinfunction "4_4") (pintype "passive"))
      (node (ref "X1") (pin "S1") (pinfunction "S1_S1") (pintype "passive"))
      (node (ref "X1") (pin "S2") (pinfunction "S2_S2") (pintype "passive"))
    )
    (net (code "43") (name "Net-(12VAC-Pad1)") (class "Default")
      (node (ref "12VAC") (pin "1") (pinfunction "1_1") (pintype "passive"))
      (node (ref "D51") (pin "A") (pinfunction "A_A") (pintype "passive"))
      (node (ref "D53") (pin "C") (pinfunction "C_C") (pintype "passive"))
    )
    (net (code "44") (name "Net-(12VAC-Pad2)") (class "Default")
      (node (ref "12VAC") (pin "2") (pinfunction "2_2") (pintype "passive"))
      (node (ref "D50") (pin "A") (pinfunction "A_A") (pintype "passive"))
      (node (ref "D52") (pin "C") (pinfunction "C_C") (pintype "passive"))
    )
    (net (code "45") (name "Net-(ASENSOR-Pad3)") (class "Default")
      (node (ref "ASENSOR") (pin "3") (pinfunction "3_3") (pintype "passive"))
      (node (ref "ASENSORH") (pin "3") (pinfunction "3_3") (pintype "passive"))
      (node (ref "L1") (pin "2") (pinfunction "2_2") (pintype "passive"))
    )
    (net (code "46") (name "Net-(F100-Pad2)") (class "Default")
      (node (ref "F100") (pin "2") (pinfunction "2_2") (pintype "passive"))
      (node (ref "X1") (pin "1") (pinfunction "1_1") (pintype "passive"))
    )
    (net (code "47") (name "Net-(IC1-PB6)") (class "Default")
      (node (ref "C21") (pin "2") (pinfunction "2_2") (pintype "passive"))
      (node (ref "IC1") (pin "9") (pinfunction "PB6_9") (pintype "bidirectional"))
      (node (ref "Q20") (pin "2") (pinfunction "2_2") (pintype "passive"))
    )
    (net (code "48") (name "Net-(IC1-PB7)") (class "Default")
      (node (ref "C22") (pin "2") (pinfunction "2_2") (pintype "passive"))
      (node (ref "IC1") (pin "10") (pinfunction "PB7_10") (pintype "bidirectional"))
      (node (ref "Q20") (pin "1") (pinfunction "1_1") (pintype "passive"))
    )
    (net (code "49") (name "Net-(IC2-OSC1{slash}CLKIN)") (class "Default")
      (node (ref "C31") (pin "2") (pinfunction "2_2") (pintype "passive"))
      (node (ref "IC2") (pin "13") (pinfunction "OSC1/CLKIN_13") (pintype "input"))
      (node (ref "Q30") (pin "2") (pinfunction "2_2") (pintype "passive"))
    )
    (net (code "50") (name "Net-(IC2-OSC2{slash}CLKOUT)") (class "Default")
      (node (ref "C32") (pin "2") (pinfunction "2_2") (pintype "passive"))
      (node (ref "IC2") (pin "14") (pinfunction "OSC2/CLKOUT_14") (pintype "output"))
      (node (ref "Q30") (pin "1") (pinfunction "1_1") (pintype "passive"))
    )
    (net (code "51") (name "Net-(IC3-GND)") (class "Default")
      (node (ref "C50") (pin "-") (pinfunction "-_-") (pintype "passive"))
      (node (ref "C51") (pin "1") (pinfunction "1_1") (pintype "passive"))
      (node (ref "C52") (pin "1") (pinfunction "1_1") (pintype "passive"))
      (node (ref "D52") (pin "A") (pinfunction "A_A") (pintype "passive"))
      (node (ref "D53") (pin "A") (pinfunction "A_A") (pintype "passive"))
      (node (ref "IC3") (pin "2") (pinfunction "GND_2") (pintype "passive"))
      (node (ref "USEVAC2") (pin "2") (pinfunction "2_2") (pintype "passive"))
    )
    (net (code "52") (name "Net-(IC3-VI)") (class "Default")
      (node (ref "C50") (pin "+") (pinfunction "+_+") (pintype "passive"))
      (node (ref "C51") (pin "2") (pinfunction "2_2") (pintype "passive"))
      (node (ref "D50") (pin "C") (pinfunction "C_C") (pintype "passive"))
      (node (ref "D51") (pin "C") (pinfunction "C_C") (pintype "passive"))
      (node (ref "IC3") (pin "1") (pinfunction "VI_1") (pintype "input"))
    )
    (net (code "53") (name "Net-(IC3-VO)") (class "Default")
      (node (ref "C52") (pin "2") (pinfunction "2_2") (pintype "passive"))
      (node (ref "IC3") (pin "3") (pinfunction "VO_3") (pintype "passive"))
      (node (ref "USEVAC1") (pin "2") (pinfunction "2_2") (pintype "passive"))
    )
    (net (code "54") (name "Net-(IC4-3V3OUT)") (class "Default")
      (node (ref "C100") (pin "2") (pinfunction "2_2") (pintype "passive"))
      (node (ref "IC4") (pin "17") (pinfunction "3V3OUT_17") (pintype "output"))
    )
    (net (code "55") (name "Net-(IC4-CBUS0)") (class "Default")
      (node (ref "IC4") (pin "23") (pinfunction "CBUS0_23") (pintype "bidirectional"))
      (node (ref "LEDRX") (pin "K") (pinfunction "C_K") (pintype "passive"))
    )
    (net (code "56") (name "Net-(IC4-CBUS1)") (class "Default")
      (node (ref "IC4") (pin "22") (pinfunction "CBUS1_22") (pintype "bidirectional"))
      (node (ref "LEDTX") (pin "K") (pinfunction "C_K") (pintype "passive"))
    )
    (net (code "57") (name "Net-(IC4-RXD)") (class "Default")
      (node (ref "IC4") (pin "5") (pinfunction "RXD_5") (pintype "input"))
      (node (ref "R101") (pin "2") (pinfunction "2_2") (pintype "passive"))
    )
    (net (code "58") (name "Net-(IC4-TXD)") (class "Default")
      (node (ref "IC4") (pin "1") (pinfunction "TXD_1") (pintype "output"))
      (node (ref "R100") (pin "1") (pinfunction "1_1") (pintype "passive"))
    )
    (net (code "59") (name "Net-(IC6-TRM)") (class "Default")
      (node (ref "IC6") (pin "5") (pinfunction "TRM_5") (pintype "input"))
      (node (ref "RTRIMM") (pin "2") (pinfunction "S_2") (pintype "passive"))
    )
    (net (code "60") (name "Net-(LED0-C)") (class "Default")
      (node (ref "LED0") (pin "K") (pinfunction "C_K") (pintype "passive"))
      (node (ref "RN2") (pin "2") (pinfunction "2_2") (pintype "passive"))
    )
    (net (code "61") (name "Net-(LED1-C)") (class "Default")
      (node (ref "LED1") (pin "K") (pinfunction "C_K") (pintype "passive"))
      (node (ref "RN2") (pin "3") (pinfunction "3_3") (pintype "passive"))
    )
    (net (code "62") (name "Net-(LED2-C)") (class "Default")
      (node (ref "LED2") (pin "K") (pinfunction "C_K") (pintype "passive"))
      (node (ref "RN2") (pin "4") (pinfunction "4_4") (pintype "passive"))
    )
    (net (code "63") (name "Net-(LED3-C)") (class "Default")
      (node (ref "LED3") (pin "K") (pinfunction "C_K") (pintype "passive"))
      (node (ref "RN2") (pin "5") (pinfunction "5_5") (pintype "passive"))
    )
    (net (code "64") (name "Net-(LED4-C)") (class "Default")
      (node (ref "LED4") (pin "K") (pinfunction "C_K") (pintype "passive"))
      (node (ref "RN2") (pin "6") (pinfunction "6_6") (pintype "passive"))
    )
    (net (code "65") (name "Net-(LED5-C)") (class "Default")
      (node (ref "LED5") (pin "K") (pinfunction "C_K") (pintype "passive"))
      (node (ref "RN2") (pin "7") (pinfunction "7_7") (pintype "passive"))
    )
    (net (code "66") (name "Net-(LED6-C)") (class "Default")
      (node (ref "LED6") (pin "K") (pinfunction "C_K") (pintype "passive"))
      (node (ref "RN2") (pin "8") (pinfunction "8_8") (pintype "passive"))
    )
    (net (code "67") (name "Net-(LED7-C)") (class "Default")
      (node (ref "LED7") (pin "K") (pinfunction "C_K") (pintype "passive"))
      (node (ref "RN2") (pin "9") (pinfunction "9_9") (pintype "passive"))
    )
    (net (code "68") (name "Net-(LEDMOS-C)") (class "Default")
      (node (ref "LEDMOS") (pin "K") (pinfunction "C_K") (pintype "passive"))
      (node (ref "RN2") (pin "10") (pinfunction "10_10") (pintype "passive"))
    )
    (net (code "69") (name "Net-(LEDPWR-C)") (class "Default")
      (node (ref "LEDPWR") (pin "K") (pinfunction "C_K") (pintype "passive"))
      (node (ref "RN2") (pin "11") (pinfunction "11_11") (pintype "passive"))
    )
    (net (code "70") (name "Net-(LEDRX-PadA)") (class "Default")
      (node (ref "LEDRX") (pin "A") (pinfunction "A_A") (pintype "passive"))
      (node (ref "R102") (pin "2") (pinfunction "2_2") (pintype "passive"))
    )
    (net (code "71") (name "Net-(LEDTX-PadA)") (class "Default")
      (node (ref "LEDTX") (pin "A") (pinfunction "A_A") (pintype "passive"))
      (node (ref "R103") (pin "2") (pinfunction "2_2") (pintype "passive"))
    )
    (net (code "72") (name "Net-(OK1-A)") (class "Default")
      (node (ref "OK1") (pin "1") (pinfunction "A_1") (pintype "passive"))
      (node (ref "R41") (pin "2") (pinfunction "2_2") (pintype "passive"))
    )
    (net (code "73") (name "Net-(OK1-EMIT)") (class "Default")
      (node (ref "OK1") (pin "3") (pinfunction "EMIT_3") (pintype "passive"))
      (node (ref "Q2") (pin "G") (pinfunction "G_G") (pintype "passive"))
      (node (ref "R40") (pin "2") (pinfunction "2_2") (pintype "passive"))
    )
    (net (code "74") (name "unconnected-(DCDCREG-Pad1)") (class "Default")
      (node (ref "DCDCREG") (pin "1") (pinfunction "1_1") (pintype "passive"))
    )
    (net (code "75") (name "unconnected-(IC2-RA2{slash}AN2-Pad4)") (class "Default")
      (node (ref "IC2") (pin "4") (pinfunction "RA2/AN2_4") (pintype "bidirectional"))
    )
    (net (code "76") (name "unconnected-(IC4-CBUS2-Pad13)") (class "Default")
      (node (ref "IC4") (pin "13") (pinfunction "CBUS2_13") (pintype "bidirectional"))
    )
    (net (code "77") (name "unconnected-(IC4-CBUS3-Pad14)") (class "Default")
      (node (ref "IC4") (pin "14") (pinfunction "CBUS3_14") (pintype "bidirectional"))
    )
    (net (code "78") (name "unconnected-(IC4-CBUS4-Pad12)") (class "Default")
      (node (ref "IC4") (pin "12") (pinfunction "CBUS4_12") (pintype "bidirectional"))
    )
    (net (code "79") (name "unconnected-(IC4-OSCI-Pad27)") (class "Default")
      (node (ref "IC4") (pin "27") (pinfunction "OSCI_27") (pintype "input"))
    )
    (net (code "80") (name "unconnected-(IC4-OSCO-Pad28)") (class "Default")
      (node (ref "IC4") (pin "28") (pinfunction "OSCO_28") (pintype "output"))
    )
    (net (code "81") (name "unconnected-(IC4-TEST-Pad26)") (class "Default")
      (node (ref "IC4") (pin "26") (pinfunction "TEST_26") (pintype "input"))
    )
    (net (code "82") (name "unconnected-(IC4-~{CTS}-Pad11)") (class "Default")
      (node (ref "IC4") (pin "11") (pinfunction "~{CTS}_11") (pintype "input"))
    )
    (net (code "83") (name "unconnected-(IC4-~{DCD}-Pad10)") (class "Default")
      (node (ref "IC4") (pin "10") (pinfunction "~{DCD}_10") (pintype "input"))
    )
    (net (code "84") (name "unconnected-(IC4-~{DSR}-Pad9)") (class "Default")
      (node (ref "IC4") (pin "9") (pinfunction "~{DSR}_9") (pintype "input"))
    )
    (net (code "85") (name "unconnected-(IC4-~{RI}-Pad6)") (class "Default")
      (node (ref "IC4") (pin "6") (pinfunction "~{RI}_6") (pintype "input"))
    )
    (net (code "86") (name "unconnected-(IC4-~{RTS}-Pad3)") (class "Default")
      (node (ref "IC4") (pin "3") (pinfunction "~{RTS}_3") (pintype "output"))
    )
    (net (code "87") (name "unconnected-(IC6-OPT-Pad3)") (class "Default")
      (node (ref "IC6") (pin "3") (pinfunction "OPT_3") (pintype "output"))
    )
    (net (code "88") (name "unconnected-(ICSP_ATMEGA-Pad5)") (class "Default")
      (node (ref "ICSP_ATMEGA") (pin "5") (pinfunction "5_5") (pintype "passive"))
    )
    (net (code "89") (name "unconnected-(ICSP_PIC-Pad6)") (class "Default")
      (node (ref "ICSP_PIC") (pin "6") (pinfunction "6_6") (pintype "passive"))
    )
    (net (code "90") (name "unconnected-(KK1-K-PadK1)") (class "Default")
      (node (ref "KK1") (pin "K1") (pinfunction "K_K1") (pintype "passive"))
    )
    (net (code "91") (name "unconnected-(KK1-K-PadK2)") (class "Default")
      (node (ref "KK1") (pin "K2") (pinfunction "K_K2") (pintype "passive"))
    )
    (net (code "92") (name "unconnected-(KK2-K-PadK1)") (class "Default")
      (node (ref "KK2") (pin "K1") (pinfunction "K_K1") (pintype "passive"))
    )
    (net (code "93") (name "unconnected-(KK2-K-PadK2)") (class "Default")
      (node (ref "KK2") (pin "K2") (pinfunction "K_K2") (pintype "passive"))
    )
    (net (code "94") (name "unconnected-(U$1-PadEN)") (class "Default")
      (node (ref "U$1") (pin "EN") (pinfunction "EN_EN") (pintype "bidirectional"))
    )
    (net (code "95") (name "unconnected-(U$1-PadFLT)") (class "Default")
      (node (ref "U$1") (pin "FLT") (pinfunction "FLT_FLT") (pintype "bidirectional"))
    )
    (net (code "96") (name "unconnected-(U$1-PadVM)") (class "Default")
      (node (ref "U$1") (pin "VM") (pinfunction "VM_VM") (pintype "bidirectional"))
    )
  )
)
